# STLINK-V2.net
KiCad netlist of a schematic drawn in Altium Designer
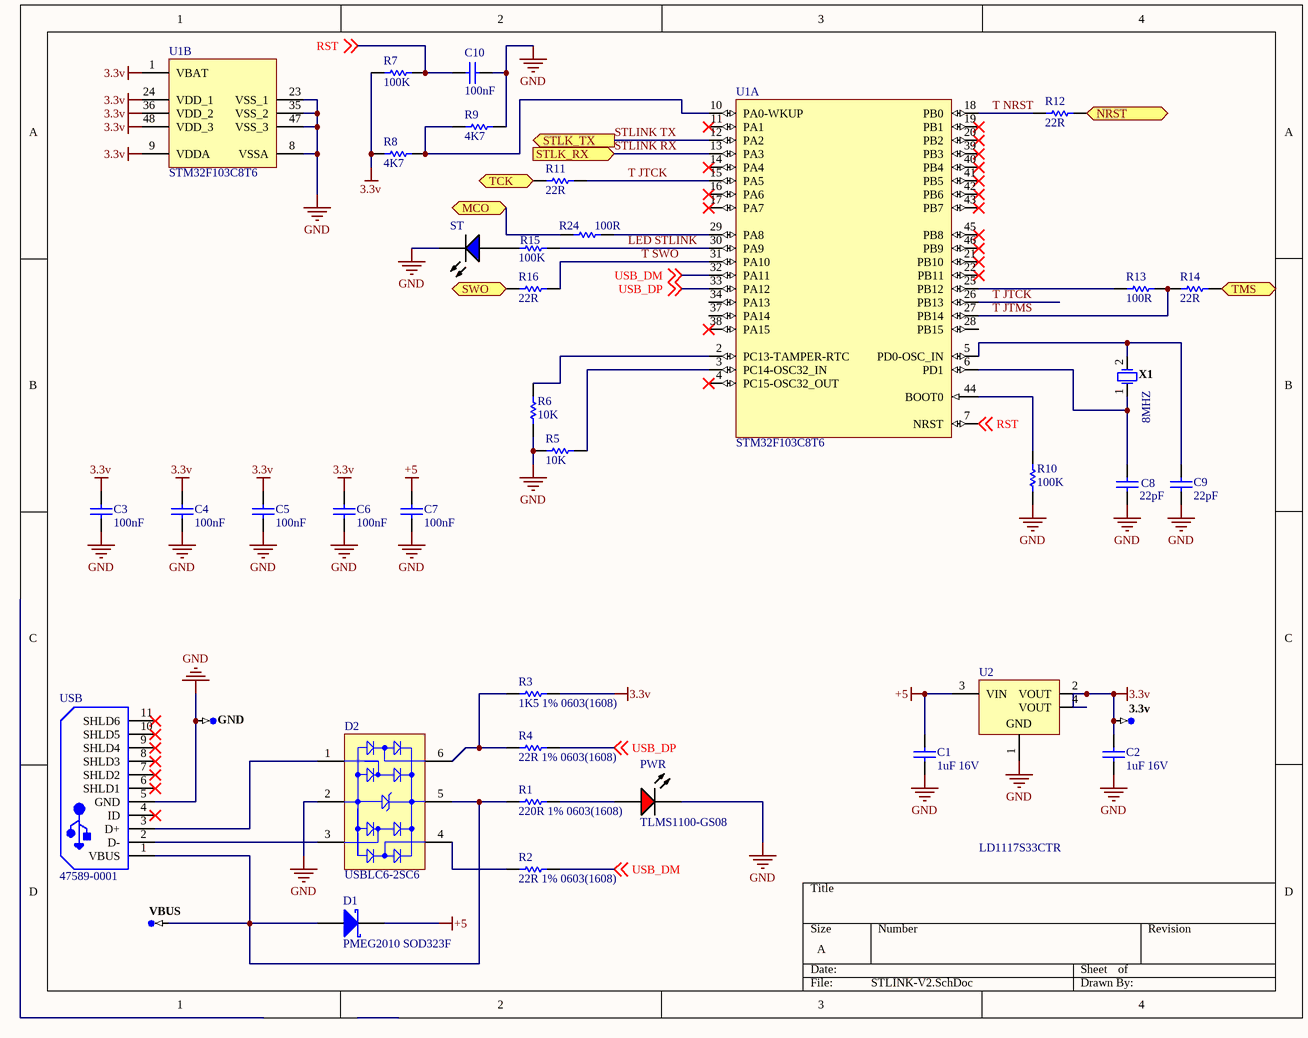
[diagram p0: STLINK-V2.SchDoc]

(export (version "E")
  (design (tool "Eeschema 10.0.6"))
  (components
    (comp (ref "3.3v")
      (value "~")
      (footprint "TP-SM-C-100")
      (description "Test Point, Surface Mount, Circular, Pad Diameter 1 mm")
      (fields (field (name "PARTNUMBER") "TP-SM-C-100") (field (name "MANUFACTURER") "No Vendor"))
      (libsource (lib "Altium Content Vault") (part "TP-SM"))
    )
    (comp (ref "C1")
      (value "1uF 16V")
      (footprint "CAPC0603(1608)100_L")
      (description "CAP 1uF 16V ±5% 0603 (1608 Metric) Thickness 1mm SMD")
      (fields (field (name "TOLERANCE") "Â±5%"))
      (libsource (lib "Altium Content Vault") (part "CAP"))
    )
    (comp (ref "C2")
      (value "1uF 16V")
      (footprint "CAPC0603(1608)100_L")
      (description "CAP 1uF 16V ±5% 0603 (1608 Metric) Thickness 1mm SMD")
      (fields (field (name "TOLERANCE") "Â±5%"))
      (libsource (lib "Altium Content Vault") (part "CAP"))
    )
    (comp (ref "C3")
      (value "100nF")
      (footprint "CAPC0603(1608)100_L")
      (description "CAP 100nF 16V ±5% 0603 (1608 Metric) Thickness 1mm SMD")
      (fields (field (name "TOLERANCE") "Â±5%"))
      (libsource (lib "Altium Content Vault") (part "CAP"))
    )
    (comp (ref "C4")
      (value "100nF")
      (footprint "CAPC0603(1608)100_L")
      (description "CAP 100nF 16V ±5% 0603 (1608 Metric) Thickness 1mm SMD")
      (fields (field (name "TOLERANCE") "Â±5%"))
      (libsource (lib "Altium Content Vault") (part "CAP"))
    )
    (comp (ref "C5")
      (value "100nF")
      (footprint "CAPC0603(1608)100_L")
      (description "CAP 100nF 16V ±5% 0603 (1608 Metric) Thickness 1mm SMD")
      (fields (field (name "TOLERANCE") "Â±5%"))
      (libsource (lib "Altium Content Vault") (part "CAP"))
    )
    (comp (ref "C6")
      (value "100nF")
      (footprint "CAPC0603(1608)100_L")
      (description "CAP 100nF 16V ±5% 0603 (1608 Metric) Thickness 1mm SMD")
      (fields (field (name "TOLERANCE") "Â±5%"))
      (libsource (lib "Altium Content Vault") (part "CAP"))
    )
    (comp (ref "C7")
      (value "100nF")
      (footprint "CAPC0603(1608)100_L")
      (description "CAP 100nF 16V ±5% 0603 (1608 Metric) Thickness 1mm SMD")
      (fields (field (name "TOLERANCE") "Â±5%"))
      (libsource (lib "Altium Content Vault") (part "CAP"))
    )
    (comp (ref "C8")
      (value "22pF")
      (footprint "CAPC0603(1608)100_L")
      (description "CAP 22pF 25V ±10% 0603 (1608 Metric) Thickness 1mm SMD")
      (fields (field (name "TOLERANCE") "Â±10%"))
      (libsource (lib "Altium Content Vault") (part "CAP"))
    )
    (comp (ref "C9")
      (value "22pF")
      (footprint "CAPC0603(1608)100_L")
      (description "CAP 22pF 25V ±10% 0603 (1608 Metric) Thickness 1mm SMD")
      (fields (field (name "TOLERANCE") "Â±10%"))
      (libsource (lib "Altium Content Vault") (part "CAP"))
    )
    (comp (ref "C10")
      (value "100nF")
      (footprint "CAPC0603(1608)100_L")
      (description "CAP 100nF 16V ±5% 0603 (1608 Metric) Thickness 1mm SMD")
      (fields (field (name "TOLERANCE") "Â±5%"))
      (libsource (lib "Altium Content Vault") (part "CAP"))
    )
    (comp (ref "D1")
      (value "PMEG2010 SOD323F")
      (footprint "NXP-SOD323F_V")
      (fields (field (name "MANUFACTURER") "NXP"))
      (libsource (lib "Altium Content Vault") (part "DSKY-KA-2"))
    )
    (comp (ref "D2")
      (value "USBLC6-2SC6")
      (footprint "STM-SOT23-6L_V")
      (description "Very low capacitance ESD protection, 3.5 pF, -40 to 125 degC, 6-Pin SOT23, RoHS, Tape and Reel")
      (fields (field (name "MANUFACTURER") "STMicroelectronics"))
      (libsource (lib "Altium Content Vault") (part "STM-USB_DVI_HDMIULC6-4SC6X-SOT23-6L"))
    )
    (comp (ref "GND")
      (value "~")
      (footprint "TP-SM-C-100")
      (description "Test Point, Surface Mount, Circular, Pad Diameter 1 mm")
      (fields (field (name "PARTNUMBER") "TP-SM-C-100") (field (name "MANUFACTURER") "No Vendor"))
      (libsource (lib "Altium Content Vault") (part "TP-SM"))
    )
    (comp (ref "PWR")
      (value "TLMS1100-GS08")
      (footprint "VISH-TLMX1100_V")
      (description "LED, RED, 2.1 V, -40 to 100 degC, 2-Pin SMD (0603), RoHS, Tape and Reel")
      (fields (field (name "TOLERANCE") "5%"))
      (libsource (lib "Altium Content Vault") (part "LED-RED-AK-2"))
    )
    (comp (ref "R1")
      (value "220R 1% 0603(1608)")
      (footprint "RESC0603(1608)_L")
      (description "220R 0.1W 1% 0603 (1608 Metric)  SMD")
      (fields (field (name "TOLERANCE") "1 %") (field (name "POWER") "0.1 W"))
      (libsource (lib "Altium Content Vault") (part "RES"))
    )
    (comp (ref "R2")
      (value "22R 1% 0603(1608)")
      (footprint "RESC0603(1608)_L")
      (description "22R 0.1W 1% 0603 (1608 Metric)  SMD")
      (fields (field (name "POWER") "0.1 W") (field (name "TOLERANCE") "1 %"))
      (libsource (lib "Altium Content Vault") (part "RES"))
    )
    (comp (ref "R3")
      (value "1K5 1% 0603(1608)")
      (footprint "RESC0603(1608)_L")
      (description "1K5 0.1W 1% 0603 (1608 Metric)  SMD")
      (fields (field (name "POWER") "0.1 W") (field (name "TOLERANCE") "1 %"))
      (libsource (lib "Altium Content Vault") (part "RES"))
    )
    (comp (ref "R4")
      (value "22R 1% 0603(1608)")
      (footprint "RESC0603(1608)_L")
      (description "22R 0.1W 1% 0603 (1608 Metric)  SMD")
      (fields (field (name "POWER") "0.1 W") (field (name "TOLERANCE") "1 %"))
      (libsource (lib "Altium Content Vault") (part "RES"))
    )
    (comp (ref "R5")
      (value "10K")
      (footprint "RESC1609X55X30LL15T15")
      (description "Chip Resistor, 10 KOhm, +/- 1%, 0.1 W, -55 to 155 degC, 0603 (1608 Metric), RoHS, Tape and Reel")
      (fields (field (name "TOLERANCE") "1%") (field (name "MANUFACTURER") "Panasonic"))
      (libsource (lib "Altium Content Vault") (part "RES-2"))
    )
    (comp (ref "R6")
      (value "10K")
      (footprint "RESC1609X55X30LL15T15")
      (description "Chip Resistor, 10 KOhm, +/- 1%, 0.1 W, -55 to 155 degC, 0603 (1608 Metric), RoHS, Tape and Reel")
      (fields (field (name "TOLERANCE") "1%") (field (name "MANUFACTURER") "Panasonic"))
      (libsource (lib "Altium Content Vault") (part "RES-2"))
    )
    (comp (ref "R7")
      (value "100K")
      (footprint "RESC0603(1608)_L")
      (description "100K 0.1W 1% 0603 (1608 Metric)  SMD")
      (fields (field (name "POWER") "0.1 W") (field (name "TOLERANCE") "1 %"))
      (libsource (lib "Altium Content Vault") (part "RES"))
    )
    (comp (ref "R8")
      (value "4K7")
      (footprint "RESC0603(1608)_L")
      (description "4K7 0.1W 1% 0603 (1608 Metric)  SMD")
      (fields (field (name "POWER") "0.1 W") (field (name "TOLERANCE") "1 %"))
      (libsource (lib "Altium Content Vault") (part "RES"))
    )
    (comp (ref "R9")
      (value "4K7")
      (footprint "RESC0603(1608)_L")
      (description "4K7 0.1W 1% 0603 (1608 Metric)  SMD")
      (fields (field (name "POWER") "0.1 W") (field (name "TOLERANCE") "1 %"))
      (libsource (lib "Altium Content Vault") (part "RES"))
    )
    (comp (ref "R10")
      (value "100K")
      (footprint "RESC0603(1608)_L")
      (description "100K 0.1W 1% 0603 (1608 Metric)  SMD")
      (fields (field (name "POWER") "0.1 W") (field (name "TOLERANCE") "1 %"))
      (libsource (lib "Altium Content Vault") (part "RES"))
    )
    (comp (ref "R11")
      (value "22R")
      (footprint "RESC0603(1608)_L")
      (description "22R 0.1W 1% 0603 (1608 Metric)  SMD")
      (fields (field (name "POWER") "0.1 W") (field (name "TOLERANCE") "1 %"))
      (libsource (lib "Altium Content Vault") (part "RES"))
    )
    (comp (ref "R12")
      (value "22R")
      (footprint "RESC0603(1608)_L")
      (description "22R 0.1W 1% 0603 (1608 Metric)  SMD")
      (fields (field (name "POWER") "0.1 W") (field (name "TOLERANCE") "1 %"))
      (libsource (lib "Altium Content Vault") (part "RES"))
    )
    (comp (ref "R13")
      (value "100R")
      (footprint "RESC0603(1608)_L")
      (description "100R 0.1W 1% 0603 (1608 Metric)  SMD")
      (fields (field (name "TOLERANCE") "1 %") (field (name "POWER") "0.1 W"))
      (libsource (lib "Altium Content Vault") (part "RES"))
    )
    (comp (ref "R14")
      (value "22R")
      (footprint "RESC0603(1608)_L")
      (description "22R 0.1W 1% 0603 (1608 Metric)  SMD")
      (fields (field (name "POWER") "0.1 W") (field (name "TOLERANCE") "1 %"))
      (libsource (lib "Altium Content Vault") (part "RES"))
    )
    (comp (ref "R15")
      (value "100K")
      (footprint "RESC0603(1608)_L")
      (description "100K 0.1W 1% 0603 (1608 Metric)  SMD")
      (fields (field (name "POWER") "0.1 W") (field (name "TOLERANCE") "1 %"))
      (libsource (lib "Altium Content Vault") (part "RES"))
    )
    (comp (ref "R16")
      (value "22R")
      (footprint "RESC0603(1608)_L")
      (description "22R 0.1W 1% 0603 (1608 Metric)  SMD")
      (fields (field (name "POWER") "0.1 W") (field (name "TOLERANCE") "1 %"))
      (libsource (lib "Altium Content Vault") (part "RES"))
    )
    (comp (ref "R24")
      (value "100R")
      (footprint "RESC0603(1608)_L")
      (description "100R 0.1W 1% 0603 (1608 Metric)  SMD")
      (fields (field (name "TOLERANCE") "1 %") (field (name "POWER") "0.1 W"))
      (libsource (lib "Altium Content Vault") (part "RES"))
    )
    (comp (ref "ST")
      (value "~")
      (footprint "ROHM-SMLE12BC7TT86_V")
      (description "Blue LED, 2.9 V, 20 mA, -30 to 85 degC, 2-Pin SMD, RoHS, Tape and Reel")
      (fields (field (name "MANUFACTURER") "Rohm"))
      (libsource (lib "Altium Content Vault") (part "LED-BLUE-AK-2"))
    )
    (comp (ref "U1")
      (value "STM32F103C8T6")
      (footprint "LQFP48_M")
      (libsource (lib "Altium Content Vault") (part "MC-ARM-STM32F101-SQ48"))
    )
    (comp (ref "U2")
      (value "LD1117S33CTR")
      (footprint "SOT-223_N")
      (description "Fixed Low Drop Positive Voltage Regulator, 3.3V, 4-Pin SOT-223, Tape and Reel")
      (libsource (lib "Altium Content Vault") (part "PM-REG-LD1117-SOT4"))
    )
    (comp (ref "USB")
      (value "47589-0001")
      (footprint "MOLX-47589-0001_V")
      (description "Right Angle Female Type AB Micro USB Connector, 30 V, 1.8 A, -30 to 85 degC, RoHS, Tape and Reel")
      (fields (field (name "MANUFACTURER") "Molex"))
      (libsource (lib "Altium Content Vault") (part "USB-5-6SHLD"))
    )
    (comp (ref "VBUS")
      (value "~")
      (footprint "TP-SM-C-100")
      (description "Test Point, Surface Mount, Circular, Pad Diameter 1 mm")
      (fields (field (name "PARTNUMBER") "TP-SM-C-100") (field (name "MANUFACTURER") "No Vendor"))
      (libsource (lib "Altium Content Vault") (part "TP-SM"))
    )
    (comp (ref "X1")
      (value "8MHZ")
      (footprint "NDK-NX3225GD-8MHZ-STD-CRA-3_V")
      (description "Crystal Unit, 8 MHz, 8 pF, -40 to 150 degC, 2-Pin SMD, RoHS, Tape and Reel")
      (fields (field (name "MANUFACTURER") "NDK"))
      (libsource (lib "Altium Content Vault") (part "XTAL-1-2-2"))
    )
  )
  (nets
    (net (code "1") (name "+5") (class "Default")
      (node (ref "C1") (pin "2") (pinfunction "2_2") (pintype "passive"))
      (node (ref "C7") (pin "2") (pinfunction "2_2") (pintype "passive"))
      (node (ref "D1") (pin "1") (pinfunction "K_1") (pintype "passive"))
      (node (ref "U2") (pin "3") (pinfunction "VIN_3") (pintype "power_in"))
    )
    (net (code "2") (name "/LED STLINK") (class "Default")
      (node (ref "R15") (pin "2") (pinfunction "2_2") (pintype "passive"))
      (node (ref "U1") (pin "30") (pinfunction "PA9_30") (pintype "bidirectional"))
    )
    (net (code "3") (name "/MCO") (class "Default")
      (node (ref "R24") (pin "1") (pinfunction "1_1") (pintype "passive"))
    )
    (net (code "4") (name "/NRST") (class "Default")
      (node (ref "R12") (pin "2") (pinfunction "2_2") (pintype "passive"))
    )
    (net (code "5") (name "/STLINK RX") (class "Default")
      (node (ref "U1") (pin "13") (pinfunction "PA3_13") (pintype "bidirectional"))
    )
    (net (code "6") (name "/STLINK TX") (class "Default")
      (node (ref "U1") (pin "12") (pinfunction "PA2_12") (pintype "bidirectional"))
    )
    (net (code "7") (name "/SWO") (class "Default")
      (node (ref "R16") (pin "1") (pinfunction "1_1") (pintype "passive"))
    )
    (net (code "8") (name "/T JTCK") (class "Default")
      (node (ref "R11") (pin "2") (pinfunction "2_2") (pintype "passive"))
      (node (ref "U1") (pin "15") (pinfunction "PA5_15") (pintype "bidirectional"))
      (node (ref "U1") (pin "26") (pinfunction "PB13_26") (pintype "bidirectional"))
    )
    (net (code "9") (name "/T JTMS") (class "Default")
      (node (ref "R13") (pin "2") (pinfunction "2_2") (pintype "passive"))
      (node (ref "R14") (pin "1") (pinfunction "1_1") (pintype "passive"))
      (node (ref "U1") (pin "27") (pinfunction "PB14_27") (pintype "bidirectional"))
    )
    (net (code "10") (name "/T NRST") (class "Default")
      (node (ref "R12") (pin "1") (pinfunction "1_1") (pintype "passive"))
      (node (ref "U1") (pin "18") (pinfunction "PB0_18") (pintype "bidirectional"))
    )
    (net (code "11") (name "/T SWO") (class "Default")
      (node (ref "R16") (pin "2") (pinfunction "2_2") (pintype "passive"))
      (node (ref "U1") (pin "31") (pinfunction "PA10_31") (pintype "bidirectional"))
    )
    (net (code "12") (name "/TCK") (class "Default")
      (node (ref "R11") (pin "1") (pinfunction "1_1") (pintype "passive"))
    )
    (net (code "13") (name "/TMS") (class "Default")
      (node (ref "R14") (pin "2") (pinfunction "2_2") (pintype "passive"))
    )
    (net (code "14") (name "3.3v") (class "Default")
      (node (ref "3.3v") (pin "1") (pinfunction "1_1") (pintype "input"))
      (node (ref "C2") (pin "2") (pinfunction "2_2") (pintype "passive"))
      (node (ref "C3") (pin "2") (pinfunction "2_2") (pintype "passive"))
      (node (ref "C4") (pin "2") (pinfunction "2_2") (pintype "passive"))
      (node (ref "C5") (pin "2") (pinfunction "2_2") (pintype "passive"))
      (node (ref "C6") (pin "2") (pinfunction "2_2") (pintype "passive"))
      (node (ref "R3") (pin "2") (pinfunction "2_2") (pintype "passive"))
      (node (ref "R7") (pin "1") (pinfunction "1_1") (pintype "passive"))
      (node (ref "R8") (pin "1") (pinfunction "1_1") (pintype "passive"))
      (node (ref "U1") (pin "1") (pinfunction "VBAT_1") (pintype "power_in"))
      (node (ref "U1") (pin "24") (pinfunction "VDD_1_24") (pintype "power_in"))
      (node (ref "U1") (pin "36") (pinfunction "VDD_2_36") (pintype "power_in"))
      (node (ref "U1") (pin "48") (pinfunction "VDD_3_48") (pintype "power_in"))
      (node (ref "U1") (pin "9") (pinfunction "VDDA_9") (pintype "power_in"))
      (node (ref "U2") (pin "2") (pinfunction "VOUT_2") (pintype "power_in"))
      (node (ref "U2") (pin "4") (pinfunction "VOUT_4") (pintype "power_in"))
    )
    (net (code "15") (name "GND") (class "Default")
      (node (ref "C1") (pin "1") (pinfunction "1_1") (pintype "passive"))
      (node (ref "C10") (pin "1") (pinfunction "1_1") (pintype "passive"))
      (node (ref "C2") (pin "1") (pinfunction "1_1") (pintype "passive"))
      (node (ref "C3") (pin "1") (pinfunction "1_1") (pintype "passive"))
      (node (ref "C4") (pin "1") (pinfunction "1_1") (pintype "passive"))
      (node (ref "C5") (pin "1") (pinfunction "1_1") (pintype "passive"))
      (node (ref "C6") (pin "1") (pinfunction "1_1") (pintype "passive"))
      (node (ref "C7") (pin "1") (pinfunction "1_1") (pintype "passive"))
      (node (ref "C8") (pin "1") (pinfunction "1_1") (pintype "passive"))
      (node (ref "C9") (pin "1") (pinfunction "1_1") (pintype "passive"))
      (node (ref "D2") (pin "2") (pinfunction "GND_2") (pintype "passive"))
      (node (ref "GND") (pin "1") (pinfunction "1_1") (pintype "input"))
      (node (ref "PWR") (pin "2") (pinfunction "K_2") (pintype "passive"))
      (node (ref "R10") (pin "1") (pinfunction "1_1") (pintype "passive"))
      (node (ref "R5") (pin "1") (pinfunction "1_1") (pintype "passive"))
      (node (ref "R6") (pin "1") (pinfunction "1_1") (pintype "passive"))
      (node (ref "R9") (pin "2") (pinfunction "2_2") (pintype "passive"))
      (node (ref "ST") (pin "2") (pinfunction "K_2") (pintype "passive"))
      (node (ref "U1") (pin "23") (pinfunction "VSS_1_23") (pintype "power_in"))
      (node (ref "U1") (pin "35") (pinfunction "VSS_2_35") (pintype "power_in"))
      (node (ref "U1") (pin "47") (pinfunction "VSS_3_47") (pintype "power_in"))
      (node (ref "U1") (pin "8") (pinfunction "VSSA_8") (pintype "power_in"))
      (node (ref "U2") (pin "1") (pinfunction "GND_1") (pintype "power_in"))
      (node (ref "USB") (pin "5") (pinfunction "GND_5") (pintype "passive"))
    )
    (net (code "16") (name "Net-(D1-A)") (class "Default")
      (node (ref "D1") (pin "2") (pinfunction "A_2") (pintype "passive"))
      (node (ref "D2") (pin "5") (pinfunction "VBUS_5") (pintype "passive"))
      (node (ref "R1") (pin "1") (pinfunction "1_1") (pintype "passive"))
      (node (ref "USB") (pin "1") (pinfunction "VBUS_1") (pintype "passive"))
      (node (ref "VBUS") (pin "1") (pinfunction "1_1") (pintype "input"))
    )
    (net (code "17") (name "Net-(D2-I{slash}O_1)") (class "Default")
      (node (ref "D2") (pin "1") (pinfunction "I/O_1_1") (pintype "passive"))
      (node (ref "USB") (pin "3") (pinfunction "D+_3") (pintype "passive"))
    )
    (net (code "18") (name "Net-(D2-I{slash}O_2)") (class "Default")
      (node (ref "D2") (pin "3") (pinfunction "I/O_2_3") (pintype "passive"))
      (node (ref "USB") (pin "2") (pinfunction "D-_2") (pintype "passive"))
    )
    (net (code "19") (name "Net-(D2-I{slash}O_3)") (class "Default")
      (node (ref "D2") (pin "4") (pinfunction "I/O_3_4") (pintype "passive"))
      (node (ref "R2") (pin "1") (pinfunction "1_1") (pintype "passive"))
    )
    (net (code "20") (name "Net-(D2-I{slash}O_4)") (class "Default")
      (node (ref "D2") (pin "6") (pinfunction "I/O_4_6") (pintype "passive"))
      (node (ref "R3") (pin "1") (pinfunction "1_1") (pintype "passive"))
      (node (ref "R4") (pin "1") (pinfunction "1_1") (pintype "passive"))
    )
    (net (code "21") (name "Net-(PWR-A)") (class "Default")
      (node (ref "PWR") (pin "1") (pinfunction "A_1") (pintype "passive"))
      (node (ref "R1") (pin "2") (pinfunction "2_2") (pintype "passive"))
    )
    (net (code "22") (name "Net-(ST-A)") (class "Default")
      (node (ref "R15") (pin "1") (pinfunction "1_1") (pintype "passive"))
      (node (ref "ST") (pin "1") (pinfunction "A_1") (pintype "passive"))
    )
    (net (code "23") (name "Net-(U1A-BOOT0)") (class "Default")
      (node (ref "R10") (pin "2") (pinfunction "2_2") (pintype "passive"))
      (node (ref "U1") (pin "44") (pinfunction "BOOT0_44") (pintype "input"))
    )
    (net (code "24") (name "Net-(U1A-PA0-WKUP)") (class "Default")
      (node (ref "R8") (pin "2") (pinfunction "2_2") (pintype "passive"))
      (node (ref "R9") (pin "1") (pinfunction "1_1") (pintype "passive"))
      (node (ref "U1") (pin "10") (pinfunction "PA0-WKUP_10") (pintype "bidirectional"))
    )
    (net (code "25") (name "Net-(U1A-PA8)") (class "Default")
      (node (ref "R24") (pin "2") (pinfunction "2_2") (pintype "passive"))
      (node (ref "U1") (pin "29") (pinfunction "PA8_29") (pintype "bidirectional"))
    )
    (net (code "26") (name "Net-(U1A-PB12)") (class "Default")
      (node (ref "R13") (pin "1") (pinfunction "1_1") (pintype "passive"))
      (node (ref "U1") (pin "25") (pinfunction "PB12_25") (pintype "bidirectional"))
    )
    (net (code "27") (name "Net-(U1A-PC13-TAMPER-RTC)") (class "Default")
      (node (ref "R6") (pin "2") (pinfunction "2_2") (pintype "passive"))
      (node (ref "U1") (pin "2") (pinfunction "PC13-TAMPER-RTC_2") (pintype "bidirectional"))
    )
    (net (code "28") (name "Net-(U1A-PC14-OSC32_IN)") (class "Default")
      (node (ref "R5") (pin "2") (pinfunction "2_2") (pintype "passive"))
      (node (ref "U1") (pin "3") (pinfunction "PC14-OSC32_IN_3") (pintype "bidirectional"))
    )
    (net (code "29") (name "Net-(U1A-PD0-OSC_IN)") (class "Default")
      (node (ref "C9") (pin "2") (pinfunction "2_2") (pintype "passive"))
      (node (ref "U1") (pin "5") (pinfunction "PD0-OSC_IN_5") (pintype "bidirectional"))
      (node (ref "X1") (pin "2") (pinfunction "2_2") (pintype "passive"))
    )
    (net (code "30") (name "Net-(U1A-PD1)") (class "Default")
      (node (ref "C8") (pin "2") (pinfunction "2_2") (pintype "passive"))
      (node (ref "U1") (pin "6") (pinfunction "PD1_6") (pintype "bidirectional"))
      (node (ref "X1") (pin "1") (pinfunction "1_1") (pintype "passive"))
    )
    (net (code "31") (name "RST") (class "Default")
      (node (ref "C10") (pin "2") (pinfunction "2_2") (pintype "passive"))
      (node (ref "R7") (pin "2") (pinfunction "2_2") (pintype "passive"))
      (node (ref "U1") (pin "7") (pinfunction "NRST_7") (pintype "bidirectional"))
    )
    (net (code "32") (name "USB_DM") (class "Default")
      (node (ref "R2") (pin "2") (pinfunction "2_2") (pintype "passive"))
      (node (ref "U1") (pin "32") (pinfunction "PA11_32") (pintype "bidirectional"))
    )
    (net (code "33") (name "USB_DP") (class "Default")
      (node (ref "R4") (pin "2") (pinfunction "2_2") (pintype "passive"))
      (node (ref "U1") (pin "33") (pinfunction "PA12_33") (pintype "bidirectional"))
    )
    (net (code "34") (name "unconnected-(U1A-PA1-Pad11)") (class "Default")
      (node (ref "U1") (pin "11") (pinfunction "PA1_11") (pintype "bidirectional+no_connect"))
    )
    (net (code "35") (name "unconnected-(U1A-PA4-Pad14)") (class "Default")
      (node (ref "U1") (pin "14") (pinfunction "PA4_14") (pintype "bidirectional+no_connect"))
    )
    (net (code "36") (name "unconnected-(U1A-PA6-Pad16)") (class "Default")
      (node (ref "U1") (pin "16") (pinfunction "PA6_16") (pintype "bidirectional+no_connect"))
    )
    (net (code "37") (name "unconnected-(U1A-PA7-Pad17)") (class "Default")
      (node (ref "U1") (pin "17") (pinfunction "PA7_17") (pintype "bidirectional+no_connect"))
    )
    (net (code "38") (name "unconnected-(U1A-PA13-Pad34)") (class "Default")
      (node (ref "U1") (pin "34") (pinfunction "PA13_34") (pintype "bidirectional"))
    )
    (net (code "39") (name "unconnected-(U1A-PA14-Pad37)") (class "Default")
      (node (ref "U1") (pin "37") (pinfunction "PA14_37") (pintype "bidirectional"))
    )
    (net (code "40") (name "unconnected-(U1A-PA15-Pad38)") (class "Default")
      (node (ref "U1") (pin "38") (pinfunction "PA15_38") (pintype "bidirectional+no_connect"))
    )
    (net (code "41") (name "unconnected-(U1A-PB1-Pad19)") (class "Default")
      (node (ref "U1") (pin "19") (pinfunction "PB1_19") (pintype "bidirectional+no_connect"))
    )
    (net (code "42") (name "unconnected-(U1A-PB2-Pad20)") (class "Default")
      (node (ref "U1") (pin "20") (pinfunction "PB2_20") (pintype "bidirectional+no_connect"))
    )
    (net (code "43") (name "unconnected-(U1A-PB3-Pad39)") (class "Default")
      (node (ref "U1") (pin "39") (pinfunction "PB3_39") (pintype "bidirectional+no_connect"))
    )
    (net (code "44") (name "unconnected-(U1A-PB4-Pad40)") (class "Default")
      (node (ref "U1") (pin "40") (pinfunction "PB4_40") (pintype "bidirectional+no_connect"))
    )
    (net (code "45") (name "unconnected-(U1A-PB5-Pad41)") (class "Default")
      (node (ref "U1") (pin "41") (pinfunction "PB5_41") (pintype "bidirectional+no_connect"))
    )
    (net (code "46") (name "unconnected-(U1A-PB6-Pad42)") (class "Default")
      (node (ref "U1") (pin "42") (pinfunction "PB6_42") (pintype "bidirectional+no_connect"))
    )
    (net (code "47") (name "unconnected-(U1A-PB7-Pad43)") (class "Default")
      (node (ref "U1") (pin "43") (pinfunction "PB7_43") (pintype "bidirectional+no_connect"))
    )
    (net (code "48") (name "unconnected-(U1A-PB8-Pad45)") (class "Default")
      (node (ref "U1") (pin "45") (pinfunction "PB8_45") (pintype "bidirectional+no_connect"))
    )
    (net (code "49") (name "unconnected-(U1A-PB9-Pad46)") (class "Default")
      (node (ref "U1") (pin "46") (pinfunction "PB9_46") (pintype "bidirectional+no_connect"))
    )
    (net (code "50") (name "unconnected-(U1A-PB10-Pad21)") (class "Default")
      (node (ref "U1") (pin "21") (pinfunction "PB10_21") (pintype "bidirectional+no_connect"))
    )
    (net (code "51") (name "unconnected-(U1A-PB11-Pad22)") (class "Default")
      (node (ref "U1") (pin "22") (pinfunction "PB11_22") (pintype "bidirectional+no_connect"))
    )
    (net (code "52") (name "unconnected-(U1A-PB15-Pad28)") (class "Default")
      (node (ref "U1") (pin "28") (pinfunction "PB15_28") (pintype "bidirectional"))
    )
    (net (code "53") (name "unconnected-(U1A-PC15-OSC32_OUT-Pad4)") (class "Default")
      (node (ref "U1") (pin "4") (pinfunction "PC15-OSC32_OUT_4") (pintype "bidirectional+no_connect"))
    )
    (net (code "54") (name "unconnected-(USB-ID-Pad4)") (class "Default")
      (node (ref "USB") (pin "4") (pinfunction "ID_4") (pintype "passive+no_connect"))
    )
    (net (code "55") (name "unconnected-(USB-SHLD1-Pad6)") (class "Default")
      (node (ref "USB") (pin "6") (pinfunction "SHLD1_6") (pintype "passive+no_connect"))
    )
    (net (code "56") (name "unconnected-(USB-SHLD2-Pad7)") (class "Default")
      (node (ref "USB") (pin "7") (pinfunction "SHLD2_7") (pintype "passive+no_connect"))
    )
    (net (code "57") (name "unconnected-(USB-SHLD3-Pad8)") (class "Default")
      (node (ref "USB") (pin "8") (pinfunction "SHLD3_8") (pintype "passive+no_connect"))
    )
    (net (code "58") (name "unconnected-(USB-SHLD4-Pad9)") (class "Default")
      (node (ref "USB") (pin "9") (pinfunction "SHLD4_9") (pintype "passive+no_connect"))
    )
    (net (code "59") (name "unconnected-(USB-SHLD5-Pad10)") (class "Default")
      (node (ref "USB") (pin "10") (pinfunction "SHLD5_10") (pintype "passive+no_connect"))
    )
    (net (code "60") (name "unconnected-(USB-SHLD6-Pad11)") (class "Default")
      (node (ref "USB") (pin "11") (pinfunction "SHLD6_11") (pintype "passive+no_connect"))
    )
  )
)
